# SCH_NFCard-Zain_2024-10-10.net
KiCad netlist of a schematic drawn in EasyEDA
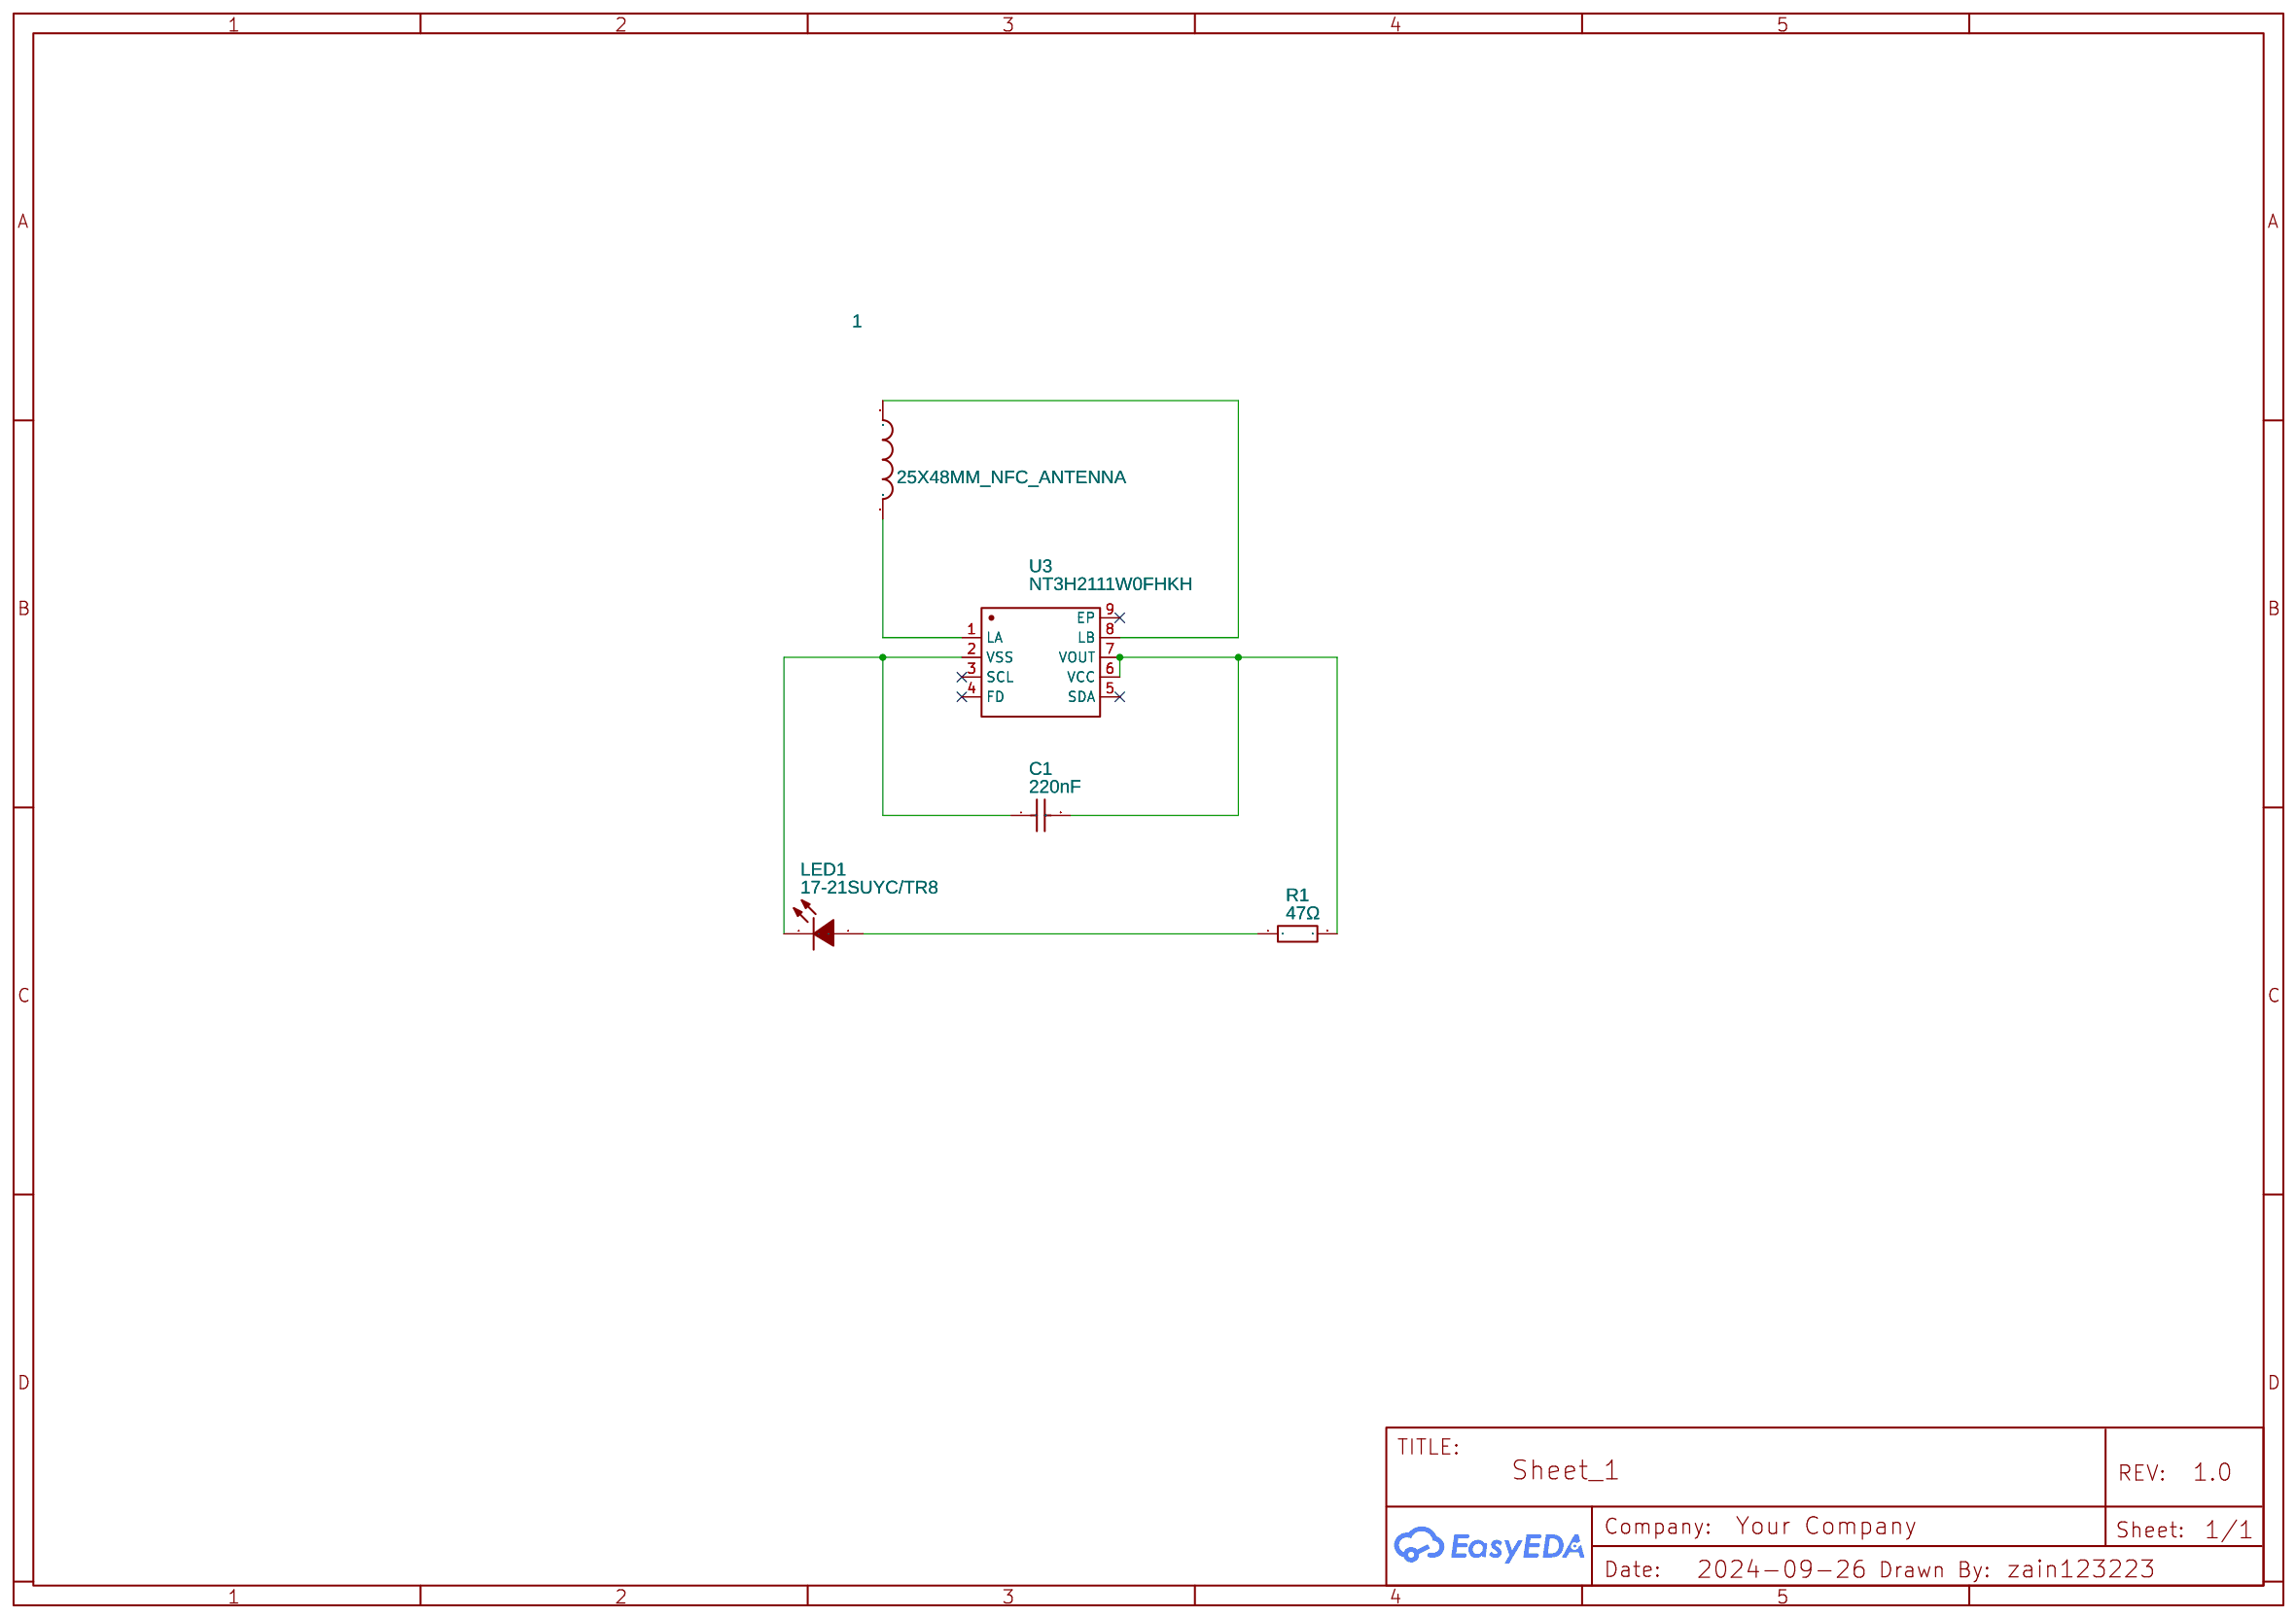
[diagram p0: schematic sheet]

(export (version "E")
  (design (tool "Eeschema 10.0.6"))
  (components
    (comp (ref "1") (value "25X48MM_NFC_ANTENNA") (libsource (lib "") (part "25X48MM_NFC_ANTENNA")))
    (comp (ref "C1")
      (value "220nF")
      (fields
        (field (name "Manufacturer Part") "CL10B224KA8NNNC")
        (field (name "Manufacturer") "SAMSUNG(三星)")
      )
      (libsource (lib "") (part "CL10B224KA8NNNC"))
    )
    (comp (ref "LED1")
      (value "17-21SUYC/TR8")
      (fields (field (name "Manufacturer Part") "KT-0805黄灯") (field (name "Manufacturer") "KENTO"))
      (libsource (lib "") (part "17-21SUYC/TR8"))
    )
    (comp (ref "R1")
      (value "47Ω")
      (fields
        (field (name "Manufacturer Part") "0603WAF470JT5E")
        (field (name "Manufacturer") "UNI-ROYAL(厚声)")
      )
      (libsource (lib "") (part "0603WAF470JT5E"))
    )
    (comp (ref "U3")
      (value "NT3H2111W0FHKH")
      (fields (field (name "Manufacturer") "NXP(恩智浦)"))
      (libsource (lib "") (part "NT3H2111W0FHKH"))
    )
  )
  (nets
    (net (code "1") (name "Net-(LED1-+)") (class "Default")
      (node (ref "LED1") (pin "1") (pinfunction "+_1") (pintype "unspecified"))
      (node (ref "R1") (pin "1") (pinfunction "1_1") (pintype "input"))
    )
    (net (code "2") (name "Net-(LED1--)") (class "Default")
      (node (ref "C1") (pin "1") (pinfunction "1_1") (pintype "input"))
      (node (ref "LED1") (pin "2") (pinfunction "-_2") (pintype "unspecified"))
      (node (ref "U3") (pin "2") (pinfunction "VSS_2") (pintype "unspecified"))
    )
    (net (code "3") (name "Net-(U3-LA)") (class "Default")
      (node (ref "1") (pin "P$2") (pinfunction "P$2_P$2") (pintype "bidirectional"))
      (node (ref "U3") (pin "1") (pinfunction "LA_1") (pintype "unspecified"))
    )
    (net (code "4") (name "Net-(U3-LB)") (class "Default")
      (node (ref "1") (pin "P$1") (pinfunction "P$1_P$1") (pintype "bidirectional"))
      (node (ref "U3") (pin "8") (pinfunction "LB_8") (pintype "unspecified"))
    )
    (net (code "5") (name "Net-(U3-VCC)") (class "Default")
      (node (ref "C1") (pin "2") (pinfunction "2_2") (pintype "input"))
      (node (ref "R1") (pin "2") (pinfunction "2_2") (pintype "input"))
      (node (ref "U3") (pin "6") (pinfunction "VCC_6") (pintype "unspecified"))
      (node (ref "U3") (pin "7") (pinfunction "VOUT_7") (pintype "unspecified"))
    )
    (net (code "6") (name "unconnected-(U3-EP-Pad9)") (class "Default")
      (node (ref "U3") (pin "9") (pinfunction "EP_9") (pintype "unspecified+no_connect"))
    )
    (net (code "7") (name "unconnected-(U3-FD-Pad4)") (class "Default")
      (node (ref "U3") (pin "4") (pinfunction "FD_4") (pintype "unspecified+no_connect"))
    )
    (net (code "8") (name "unconnected-(U3-SCL-Pad3)") (class "Default")
      (node (ref "U3") (pin "3") (pinfunction "SCL_3") (pintype "unspecified+no_connect"))
    )
    (net (code "9") (name "unconnected-(U3-SDA-Pad5)") (class "Default")
      (node (ref "U3") (pin "5") (pinfunction "SDA_5") (pintype "unspecified+no_connect"))
    )
  )
)
